# USB_PD_Sink_CYPD3177.net
KiCad netlist of a schematic drawn in Altium Designer
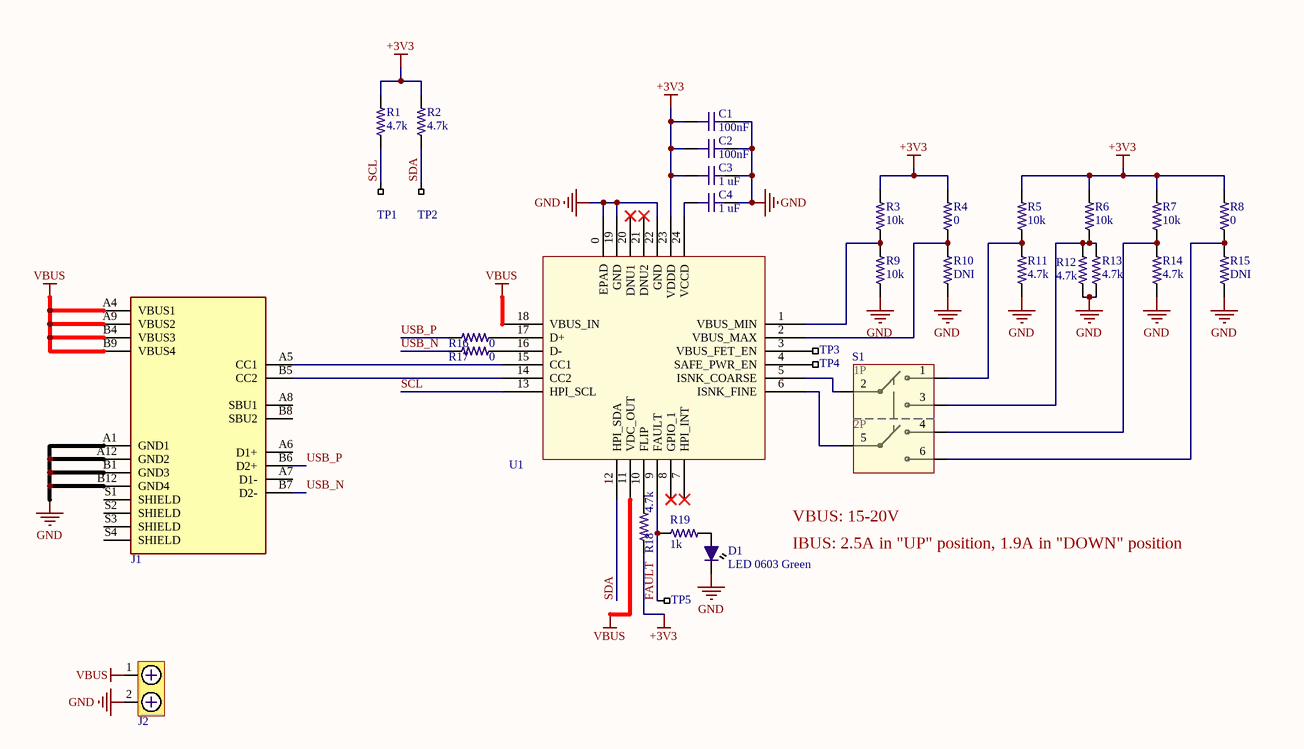
[diagram p0: USB_PD_Sink_CYPD3177.SchDoc]

(export (version "E")
  (design (tool "Eeschema 10.0.6"))
  (components
    (comp (ref "C1")
      (value "100nF")
      (footprint "C0603-IPC")
      (description "Chip Capacitor, 0603, 100nF, 25V, X7R")
      (fields (field (name "Comment") "C0603 100nF 25V X7R"))
      (libsource (lib "Capacitors") (part "C0603 100nF 25V X7R"))
    )
    (comp (ref "C2")
      (value "100nF")
      (footprint "C0603-IPC")
      (description "Chip Capacitor, 0603, 100nF, 25V, X7R")
      (fields (field (name "Comment") "C0603 100nF 25V X7R"))
      (libsource (lib "Capacitors") (part "C0603 100nF 25V X7R"))
    )
    (comp (ref "C3")
      (value "1 uF")
      (footprint "C0603-IPC")
      (description "Chip Capacitor, 0603, 1uF +/- 0.1uF, 10V, X7R")
      (fields (field (name "Comment") "C0603 1uF 10V X7R"))
      (libsource (lib "Capacitors") (part "C0603 1uF 10V X7R"))
    )
    (comp (ref "C4")
      (value "1 uF")
      (footprint "C0603-IPC")
      (description "Chip Capacitor, 0603, 1uF +/- 0.1uF, 10V, X7R")
      (fields (field (name "Comment") "C0603 1uF 10V X7R"))
      (libsource (lib "Capacitors") (part "C0603 1uF 10V X7R"))
    )
    (comp (ref "D1")
      (value "LED 0603 Green")
      (footprint "LED0603-IPC")
      (description "LED GREEN CLEAR 0603 SMD")
      (libsource (lib "Diodes") (part "LED 0603 Green"))
    )
    (comp (ref "J1")
      (value "16 Pin Mid Mount USB C")
      (footprint "Connectors:USB-C - 16 Pin Mid Mount")
      (description "USB-C USB 2.0 5A PD 16 Position Mid Mount")
      (fields (field (name "MANUFACTURER") "Jing Extension of the Electronic Co"))
      (libsource (lib "Connectors") (part "USB C USB 2.0 and PD"))
    )
    (comp (ref "J2")
      (value "Phoenix Contact 1935161")
      (footprint "Phoenix_1935161")
      (description "Terminal Block, 2 Position, 5mm pitch, 18A, 300V, 12-26 AWG")
      (fields
        (field (name "MANUFACTURER") "Phoenix Contact")
        (field (name "MANUFACTURER PART NUMBER") "1935161")
      )
      (libsource (lib "Connectors") (part "Term Block 2pos"))
    )
    (comp (ref "R1")
      (value "4.7k")
      (footprint "R0603-HIGH-DENSITY")
      (description "Chip Resistor, 0603, 4.7k ohms, 0.1W")
      (fields (field (name "Comment") "R0603 4.7k 1%"))
      (libsource (lib "Resistors") (part "R0603 4.7k 1%"))
    )
    (comp (ref "R2")
      (value "4.7k")
      (footprint "R0603-HIGH-DENSITY")
      (description "Chip Resistor, 0603, 4.7k ohms, 0.1W")
      (fields (field (name "Comment") "R0603 4.7k 1%"))
      (libsource (lib "Resistors") (part "R0603 4.7k 1%"))
    )
    (comp (ref "R3")
      (value "10k")
      (footprint "R0603-IPC")
      (description "RES SMD 10K OHM 1% 1/10W 0603")
      (fields (field (name "Comment") "R0603 10K 1%"))
      (libsource (lib "Resistors") (part "R0603 10K 1%"))
    )
    (comp (ref "R4")
      (value "0")
      (footprint "R0603-IPC")
      (description "RES SMD 0 OHM JUMPER 1/10W 0603")
      (fields (field (name "Comment") "R0603 0"))
      (libsource (lib "Resistors") (part "R0603 0"))
    )
    (comp (ref "R5")
      (value "10k")
      (footprint "R0603-IPC")
      (description "RES SMD 10K OHM 1% 1/10W 0603")
      (fields (field (name "Comment") "R0603 10K 1%"))
      (libsource (lib "Resistors") (part "R0603 10K 1%"))
    )
    (comp (ref "R6")
      (value "10k")
      (footprint "R0603-IPC")
      (description "RES SMD 10K OHM 1% 1/10W 0603")
      (fields (field (name "Comment") "R0603 10K 1%"))
      (libsource (lib "Resistors") (part "R0603 10K 1%"))
    )
    (comp (ref "R7")
      (value "10k")
      (footprint "R0603-IPC")
      (description "RES SMD 10K OHM 1% 1/10W 0603")
      (fields (field (name "Comment") "R0603 10K 1%"))
      (libsource (lib "Resistors") (part "R0603 10K 1%"))
    )
    (comp (ref "R8")
      (value "0")
      (footprint "R0603-IPC")
      (description "RES SMD 0 OHM JUMPER 1/10W 0603")
      (fields (field (name "Comment") "R0603 0"))
      (libsource (lib "Resistors") (part "R0603 0"))
    )
    (comp (ref "R9")
      (value "10k")
      (footprint "R0603-IPC")
      (description "RES SMD 10K OHM 1% 1/10W 0603")
      (fields (field (name "Comment") "R0603 10K 1%"))
      (libsource (lib "Resistors") (part "R0603 10K 1%"))
    )
    (comp (ref "R10")
      (value "DNI")
      (footprint "R0603-IPC")
      (description "RES SMD 0 OHM JUMPER 1/10W 0603")
      (fields (field (name "Comment") "R0603 0"))
      (libsource (lib "Resistors") (part "R0603 0"))
    )
    (comp (ref "R11")
      (value "4.7k")
      (footprint "R0603-IPC")
      (description "Chip Resistor, 0603, 4.7k ohms, 0.1W")
      (fields (field (name "Comment") "R0603 4.7k 1%"))
      (libsource (lib "Resistors") (part "R0603 4.7k 1%"))
    )
    (comp (ref "R12")
      (value "4.7k")
      (footprint "R0603-IPC")
      (description "Chip Resistor, 0603, 4.7k ohms, 0.1W")
      (fields (field (name "Comment") "R0603 4.7k 1%"))
      (libsource (lib "Resistors") (part "R0603 4.7k 1%"))
    )
    (comp (ref "R13")
      (value "4.7k")
      (footprint "R0603-IPC")
      (description "Chip Resistor, 0603, 4.7k ohms, 0.1W")
      (fields (field (name "Comment") "R0603 4.7k 1%"))
      (libsource (lib "Resistors") (part "R0603 4.7k 1%"))
    )
    (comp (ref "R14")
      (value "4.7k")
      (footprint "R0603-IPC")
      (description "Chip Resistor, 0603, 4.7k ohms, 0.1W")
      (fields (field (name "Comment") "R0603 4.7k 1%"))
      (libsource (lib "Resistors") (part "R0603 4.7k 1%"))
    )
    (comp (ref "R15")
      (value "DNI")
      (footprint "R0603-IPC")
      (description "RES SMD 0 OHM JUMPER 1/10W 0603")
      (fields (field (name "Comment") "R0603 0"))
      (libsource (lib "Resistors") (part "R0603 0"))
    )
    (comp (ref "R16")
      (value "0")
      (footprint "R0402-HIGH-DENSITY")
      (description "Chip Resistor, 0402, 0 ohm jumper")
      (fields (field (name "Comment") "R0402 0R"))
      (libsource (lib "Resistors") (part "R0402 0R"))
    )
    (comp (ref "R17")
      (value "0")
      (footprint "R0402-HIGH-DENSITY")
      (description "Chip Resistor, 0402, 0 ohm jumper")
      (fields (field (name "Comment") "R0402 0R"))
      (libsource (lib "Resistors") (part "R0402 0R"))
    )
    (comp (ref "R18")
      (value "4.7k")
      (footprint "R0603-HIGH-DENSITY")
      (description "Chip Resistor, 0603, 4.7k ohms, 0.1W")
      (fields (field (name "Comment") "R0603 4.7k 1%"))
      (libsource (lib "Resistors") (part "R0603 4.7k 1%"))
    )
    (comp (ref "R19")
      (value "1k")
      (footprint "R0603-IPC")
      (description "RES SMD 1K OHM 1% 1/10W 0603")
      (fields (field (name "TOLERANCE") "±1%") (field (name "Comment") "R0603 1K 1%"))
      (libsource (lib "Resistors") (part "R0603 1K 1%"))
    )
    (comp (ref "S1")
      (value "SS-3235S-L3")
      (footprint "SS-3235S-L3")
      (description "DPDT 50mA @ 12VDC 12V On-On SMD Toggle Switches RoHS")
      (libsource (lib "Switches") (part "Slide Switch DPDT SMD"))
    )
    (comp (ref "TP1")
      (value "SCL")
      (footprint "TESTPOINT_SMT")
      (description "SMT Test Point")
      (libsource (lib "Virtual Parts") (part "Testpoint_SMT"))
    )
    (comp (ref "TP2")
      (value "SDA")
      (footprint "TESTPOINT_SMT")
      (description "SMT Test Point")
      (libsource (lib "Virtual Parts") (part "Testpoint_SMT"))
    )
    (comp (ref "TP3")
      (value "VBUS_FET_EN")
      (footprint "TESTPOINT_SMT")
      (description "SMT Test Point")
      (libsource (lib "Virtual Parts") (part "Testpoint_SMT"))
    )
    (comp (ref "TP4")
      (value "SAFE_PWR_EN")
      (footprint "TESTPOINT_SMT")
      (description "SMT Test Point")
      (libsource (lib "Virtual Parts") (part "Testpoint_SMT"))
    )
    (comp (ref "TP5")
      (value "FAULT")
      (footprint "TESTPOINT_SMT")
      (description "SMT Test Point")
      (libsource (lib "Virtual Parts") (part "Testpoint_SMT"))
    )
    (comp (ref "U1")
      (value "CYPD3177 PD Sink Controller")
      (footprint "QFN24 - 4X4MM - PITCH 0.5MM - EXPOSEDPAD")
      (description "IC USB TYPE-C PD PORT CONTROL 24QFN")
      (libsource (lib "Integrated Circuits") (part "CYPD3177"))
    )
  )
  (nets
    (net (code "1") (name "+3V3") (class "Default")
      (node (ref "C1") (pin "1") (pintype "passive"))
      (node (ref "C2") (pin "1") (pintype "passive"))
      (node (ref "C3") (pin "2") (pintype "passive"))
      (node (ref "R1") (pin "1") (pintype "passive"))
      (node (ref "R18") (pin "2") (pintype "passive"))
      (node (ref "R2") (pin "1") (pintype "passive"))
      (node (ref "R3") (pin "2") (pintype "passive"))
      (node (ref "R4") (pin "2") (pintype "passive"))
      (node (ref "R5") (pin "2") (pintype "passive"))
      (node (ref "R6") (pin "2") (pintype "passive"))
      (node (ref "R7") (pin "2") (pintype "passive"))
      (node (ref "R8") (pin "2") (pintype "passive"))
      (node (ref "U1") (pin "23") (pinfunction "VDDD_23") (pintype "passive"))
    )
    (net (code "2") (name "/FAULT") (class "Default")
      (node (ref "R19") (pin "1") (pintype "passive"))
      (node (ref "TP5") (pin "1") (pinfunction "1_1") (pintype "passive"))
      (node (ref "U1") (pin "9") (pinfunction "FAULT_9") (pintype "passive"))
    )
    (net (code "3") (name "/SCL") (class "Default")
      (node (ref "R1") (pin "2") (pintype "passive"))
      (node (ref "TP1") (pin "1") (pinfunction "1_1") (pintype "passive"))
      (node (ref "U1") (pin "13") (pinfunction "HPI_SCL_13") (pintype "passive"))
    )
    (net (code "4") (name "/SDA") (class "Default")
      (node (ref "R2") (pin "2") (pintype "passive"))
      (node (ref "TP2") (pin "1") (pinfunction "1_1") (pintype "passive"))
      (node (ref "U1") (pin "12") (pinfunction "HPI_SDA_12") (pintype "passive"))
    )
    (net (code "5") (name "/USB_N") (class "Default")
      (node (ref "J1") (pin "B7") (pinfunction "D2-_B7") (pintype "passive"))
      (node (ref "R17") (pin "1") (pintype "passive"))
    )
    (net (code "6") (name "/USB_P") (class "Default")
      (node (ref "J1") (pin "B6") (pinfunction "D2+_B6") (pintype "passive"))
      (node (ref "R16") (pin "1") (pintype "passive"))
    )
    (net (code "7") (name "GND") (class "Default")
      (node (ref "C1") (pin "2") (pintype "passive"))
      (node (ref "C2") (pin "2") (pintype "passive"))
      (node (ref "C3") (pin "1") (pintype "passive"))
      (node (ref "C4") (pin "1") (pintype "passive"))
      (node (ref "D1") (pin "K") (pintype "passive"))
      (node (ref "J1") (pin "A1") (pinfunction "GND1_A1") (pintype "passive"))
      (node (ref "J1") (pin "A12") (pinfunction "GND2_A12") (pintype "passive"))
      (node (ref "J1") (pin "B1") (pinfunction "GND3_B1") (pintype "passive"))
      (node (ref "J1") (pin "B12") (pinfunction "GND4_B12") (pintype "passive"))
      (node (ref "J2") (pin "2") (pintype "passive"))
      (node (ref "R10") (pin "1") (pintype "passive"))
      (node (ref "R11") (pin "1") (pintype "passive"))
      (node (ref "R12") (pin "1") (pintype "passive"))
      (node (ref "R13") (pin "1") (pintype "passive"))
      (node (ref "R14") (pin "1") (pintype "passive"))
      (node (ref "R15") (pin "1") (pintype "passive"))
      (node (ref "R9") (pin "1") (pintype "passive"))
      (node (ref "U1") (pin "0") (pinfunction "EPAD_0") (pintype "passive"))
      (node (ref "U1") (pin "19") (pinfunction "GND_19") (pintype "passive"))
      (node (ref "U1") (pin "22") (pinfunction "GND_22") (pintype "passive"))
    )
    (net (code "8") (name "Net-(D1-PadA)") (class "Default")
      (node (ref "D1") (pin "A") (pintype "passive"))
      (node (ref "R19") (pin "2") (pintype "passive"))
    )
    (net (code "9") (name "Net-(J1-CC1)") (class "Default")
      (node (ref "J1") (pin "A5") (pinfunction "CC1_A5") (pintype "passive"))
      (node (ref "U1") (pin "15") (pinfunction "CC1_15") (pintype "passive"))
    )
    (net (code "10") (name "Net-(J1-CC2)") (class "Default")
      (node (ref "J1") (pin "B5") (pinfunction "CC2_B5") (pintype "passive"))
      (node (ref "U1") (pin "14") (pinfunction "CC2_14") (pintype "passive"))
    )
    (net (code "11") (name "Net-(R11-Pad2)") (class "Default")
      (node (ref "R11") (pin "2") (pintype "passive"))
      (node (ref "R5") (pin "1") (pintype "passive"))
      (node (ref "S1") (pin "1") (pintype "passive"))
    )
    (net (code "12") (name "Net-(R12-Pad2)") (class "Default")
      (node (ref "R12") (pin "2") (pintype "passive"))
      (node (ref "R13") (pin "2") (pintype "passive"))
      (node (ref "R6") (pin "1") (pintype "passive"))
      (node (ref "S1") (pin "3") (pintype "passive"))
    )
    (net (code "13") (name "Net-(R14-Pad2)") (class "Default")
      (node (ref "R14") (pin "2") (pintype "passive"))
      (node (ref "R7") (pin "1") (pintype "passive"))
      (node (ref "S1") (pin "4") (pintype "passive"))
    )
    (net (code "14") (name "Net-(R15-Pad2)") (class "Default")
      (node (ref "R15") (pin "2") (pintype "passive"))
      (node (ref "R8") (pin "1") (pintype "passive"))
      (node (ref "S1") (pin "6") (pintype "passive"))
    )
    (net (code "15") (name "Net-(U1-D+)") (class "Default")
      (node (ref "R16") (pin "2") (pintype "passive"))
      (node (ref "U1") (pin "17") (pinfunction "D+_17") (pintype "passive"))
    )
    (net (code "16") (name "Net-(U1-D-)") (class "Default")
      (node (ref "R17") (pin "2") (pintype "passive"))
      (node (ref "U1") (pin "16") (pinfunction "D-_16") (pintype "passive"))
    )
    (net (code "17") (name "Net-(U1-FLIP)") (class "Default")
      (node (ref "R18") (pin "1") (pintype "passive"))
      (node (ref "U1") (pin "10") (pinfunction "FLIP_10") (pintype "passive"))
    )
    (net (code "18") (name "Net-(U1-ISNK_COARSE)") (class "Default")
      (node (ref "S1") (pin "2") (pintype "passive"))
      (node (ref "U1") (pin "5") (pinfunction "ISNK_COARSE_5") (pintype "passive"))
    )
    (net (code "19") (name "Net-(U1-ISNK_FINE)") (class "Default")
      (node (ref "S1") (pin "5") (pintype "passive"))
      (node (ref "U1") (pin "6") (pinfunction "ISNK_FINE_6") (pintype "passive"))
    )
    (net (code "20") (name "Net-(U1-SAFE_PWR_EN)") (class "Default")
      (node (ref "TP4") (pin "1") (pinfunction "1_1") (pintype "passive"))
      (node (ref "U1") (pin "4") (pinfunction "SAFE_PWR_EN_4") (pintype "passive"))
    )
    (net (code "21") (name "Net-(U1-VBUS_FET_EN)") (class "Default")
      (node (ref "TP3") (pin "1") (pinfunction "1_1") (pintype "passive"))
      (node (ref "U1") (pin "3") (pinfunction "VBUS_FET_EN_3") (pintype "passive"))
    )
    (net (code "22") (name "Net-(U1-VBUS_MAX)") (class "Default")
      (node (ref "R10") (pin "2") (pintype "passive"))
      (node (ref "R4") (pin "1") (pintype "passive"))
      (node (ref "U1") (pin "2") (pinfunction "VBUS_MAX_2") (pintype "passive"))
    )
    (net (code "23") (name "Net-(U1-VBUS_MIN)") (class "Default")
      (node (ref "R3") (pin "1") (pintype "passive"))
      (node (ref "R9") (pin "2") (pintype "passive"))
      (node (ref "U1") (pin "1") (pinfunction "VBUS_MIN_1") (pintype "passive"))
    )
    (net (code "24") (name "Net-(U1-VCCD)") (class "Default")
      (node (ref "C4") (pin "2") (pintype "passive"))
      (node (ref "U1") (pin "24") (pinfunction "VCCD_24") (pintype "passive"))
    )
    (net (code "25") (name "VBUS") (class "Default")
      (node (ref "J1") (pin "A4") (pinfunction "VBUS1_A4") (pintype "passive"))
      (node (ref "J1") (pin "A9") (pinfunction "VBUS2_A9") (pintype "passive"))
      (node (ref "J1") (pin "B4") (pinfunction "VBUS3_B4") (pintype "passive"))
      (node (ref "J1") (pin "B9") (pinfunction "VBUS4_B9") (pintype "passive"))
      (node (ref "J2") (pin "1") (pintype "passive"))
      (node (ref "U1") (pin "11") (pinfunction "VDC_OUT_11") (pintype "passive"))
      (node (ref "U1") (pin "18") (pinfunction "VBUS_IN_18") (pintype "passive"))
    )
    (net (code "26") (name "unconnected-(J1-D1+-PadA6)") (class "Default")
      (node (ref "J1") (pin "A6") (pinfunction "D1+_A6") (pintype "passive"))
    )
    (net (code "27") (name "unconnected-(J1-D1--PadA7)") (class "Default")
      (node (ref "J1") (pin "A7") (pinfunction "D1-_A7") (pintype "passive"))
    )
    (net (code "28") (name "unconnected-(J1-SBU1-PadA8)") (class "Default")
      (node (ref "J1") (pin "A8") (pinfunction "SBU1_A8") (pintype "passive"))
    )
    (net (code "29") (name "unconnected-(J1-SBU2-PadB8)") (class "Default")
      (node (ref "J1") (pin "B8") (pinfunction "SBU2_B8") (pintype "passive"))
    )
    (net (code "30") (name "unconnected-(J1-SHIELD-PadS1)") (class "Default")
      (node (ref "J1") (pin "S1") (pinfunction "SHIELD_S1") (pintype "passive"))
    )
    (net (code "31") (name "unconnected-(J1-SHIELD-PadS2)") (class "Default")
      (node (ref "J1") (pin "S2") (pinfunction "SHIELD_S2") (pintype "passive"))
    )
    (net (code "32") (name "unconnected-(J1-SHIELD-PadS3)") (class "Default")
      (node (ref "J1") (pin "S3") (pinfunction "SHIELD_S3") (pintype "passive"))
    )
    (net (code "33") (name "unconnected-(J1-SHIELD-PadS4)") (class "Default")
      (node (ref "J1") (pin "S4") (pinfunction "SHIELD_S4") (pintype "passive"))
    )
    (net (code "34") (name "unconnected-(U1-DNU1-Pad20)") (class "Default")
      (node (ref "U1") (pin "20") (pinfunction "DNU1_20") (pintype "passive+no_connect"))
    )
    (net (code "35") (name "unconnected-(U1-DNU2-Pad21)") (class "Default")
      (node (ref "U1") (pin "21") (pinfunction "DNU2_21") (pintype "passive+no_connect"))
    )
    (net (code "36") (name "unconnected-(U1-GPIO_1-Pad8)") (class "Default")
      (node (ref "U1") (pin "8") (pinfunction "GPIO_1_8") (pintype "passive+no_connect"))
    )
    (net (code "37") (name "unconnected-(U1-HPI_INT-Pad7)") (class "Default")
      (node (ref "U1") (pin "7") (pinfunction "HPI_INT_7") (pintype "passive+no_connect"))
    )
  )
)
